# MCU.net
KiCad netlist of a schematic drawn in Altium Designer
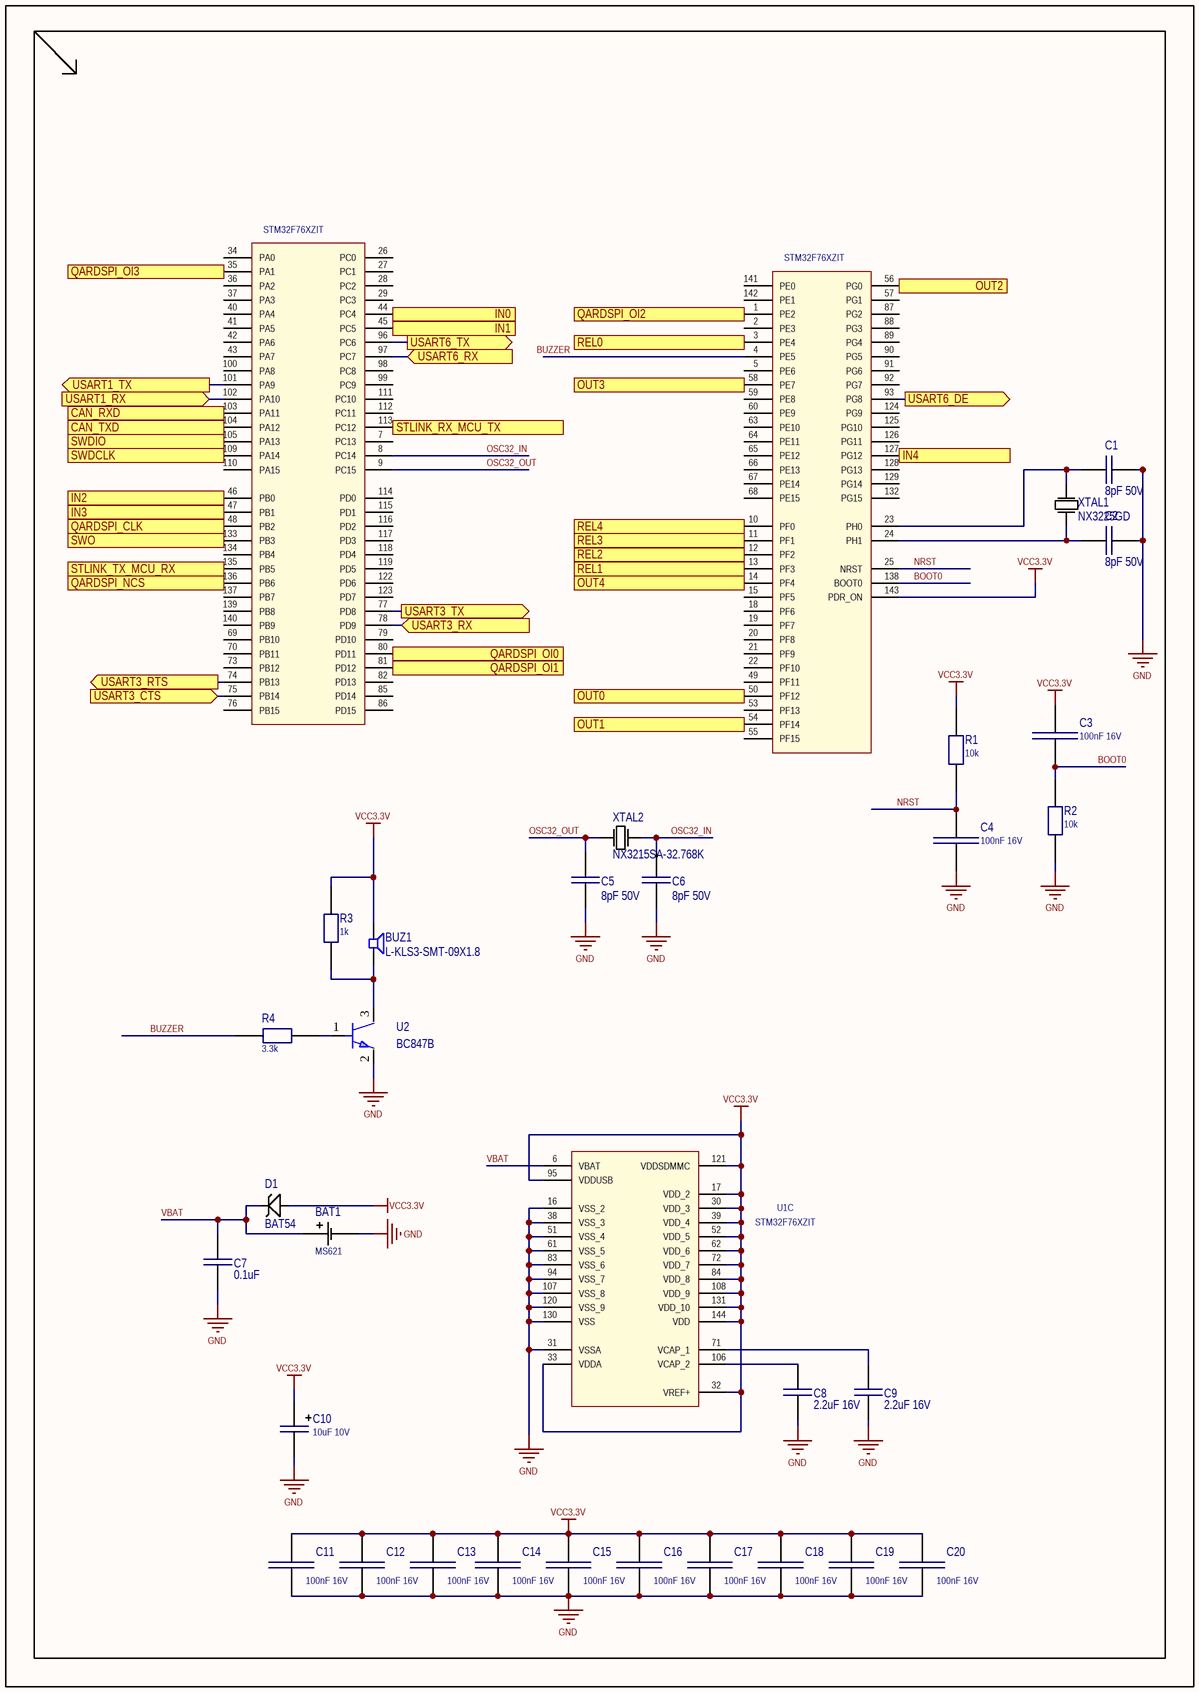
[diagram p0: MCU.SchDoc]

(export (version "E")
  (design (tool "Eeschema 10.0.6"))
  (components
    (comp (ref "BAT1")
      (value "MS621")
      (footprint "battery_socets:MS621")
      (description "Battery")
      (libsource (lib "battery_socets") (part "MS621"))
    )
    (comp (ref "BUZ1")
      (value "L-KLS3-SMT-09X1.8")
      (footprint "SPKR_PKMCS0909E4000-R1")
      (description "Piezoelectric Sounders")
      (fields (field (name "ALTERNATIVE PART") "PKLCS1212E40A1-R1"))
      (libsource (lib "other") (part "BUZZER"))
    )
    (comp (ref "C1")
      (value "8pF 50V")
      (footprint "C_0603")
      (description "Capacitor")
      (fields (field (name "PART NUMBER") "CC0603DRNPO9BN8R0"))
      (libsource (lib "capacitors") (part "CAP_SMD"))
    )
    (comp (ref "C2")
      (value "8pF 50V")
      (footprint "C_0603")
      (description "Capacitor")
      (fields (field (name "PART NUMBER") "CC0603DRNPO9BN8R0"))
      (libsource (lib "capacitors") (part "CAP_SMD"))
    )
    (comp (ref "C3")
      (value "100nF 16V")
      (footprint "C_0603")
      (description "Capacitor")
      (fields (field (name "PART NUMBER") "CC0603KPX7R9BB104"))
      (libsource (lib "AX_Altium_v2.3") (part "C0603"))
    )
    (comp (ref "C4")
      (value "100nF 16V")
      (footprint "C_0603")
      (description "Capacitor")
      (fields (field (name "PART NUMBER") "CC0603KPX7R9BB104"))
      (libsource (lib "AX_Altium_v2.3") (part "C0603"))
    )
    (comp (ref "C5")
      (value "8pF 50V")
      (footprint "C_0603")
      (description "Capacitor")
      (fields (field (name "PART NUMBER") "CC0603DRNPO9BN8R0"))
      (libsource (lib "capacitors") (part "CAP_SMD"))
    )
    (comp (ref "C6")
      (value "8pF 50V")
      (footprint "C_0603")
      (description "Capacitor")
      (fields (field (name "PART NUMBER") "CC0603DRNPO9BN8R0"))
      (libsource (lib "capacitors") (part "CAP_SMD"))
    )
    (comp (ref "C7")
      (value "0.1uF")
      (footprint "C_0603")
      (description "Capacitor")
      (fields (field (name "PART NUMBER") "CC0603KPX7R9BB104"))
      (libsource (lib "capacitors") (part "CAP_SMD"))
    )
    (comp (ref "C8")
      (value "2.2uF 16V")
      (footprint "C_0603")
      (description "Capacitor")
      (fields (field (name "PART NUMBER") "CC0603KRX5R7BB225"))
      (libsource (lib "capacitors") (part "CAP_SMD"))
    )
    (comp (ref "C9")
      (value "2.2uF 16V")
      (footprint "C_0603")
      (description "Capacitor")
      (fields (field (name "PART NUMBER") "CC0603KRX5R7BB225"))
      (libsource (lib "capacitors") (part "CAP_SMD"))
    )
    (comp (ref "C10")
      (value "10uF 10V")
      (footprint "TANTAL_TYPE_A")
      (description "Tantal Capacitor")
      (fields (field (name "PART NUMBER") "293D106X9010A2TE3"))
      (libsource (lib "capacitors") (part "TANTAL_CAP"))
    )
    (comp (ref "C11")
      (value "100nF 16V")
      (footprint "C_0603")
      (description "Capacitor")
      (fields (field (name "PART NUMBER") "CC0603KPX7R9BB104"))
      (libsource (lib "AX_Altium_v2.3") (part "C0603"))
    )
    (comp (ref "C12")
      (value "100nF 16V")
      (footprint "C_0603")
      (description "Capacitor")
      (fields (field (name "PART NUMBER") "CC0603KPX7R9BB104"))
      (libsource (lib "AX_Altium_v2.3") (part "C0603"))
    )
    (comp (ref "C13")
      (value "100nF 16V")
      (footprint "C_0603")
      (description "Capacitor")
      (fields (field (name "PART NUMBER") "CC0603KPX7R9BB104"))
      (libsource (lib "AX_Altium_v2.3") (part "C0603"))
    )
    (comp (ref "C14")
      (value "100nF 16V")
      (footprint "C_0603")
      (description "Capacitor")
      (fields (field (name "PART NUMBER") "CC0603KPX7R9BB104"))
      (libsource (lib "AX_Altium_v2.3") (part "C0603"))
    )
    (comp (ref "C15")
      (value "100nF 16V")
      (footprint "C_0603")
      (description "Capacitor")
      (fields (field (name "PART NUMBER") "CC0603KPX7R9BB104"))
      (libsource (lib "AX_Altium_v2.3") (part "C0603"))
    )
    (comp (ref "C16")
      (value "100nF 16V")
      (footprint "C_0603")
      (description "Capacitor")
      (fields (field (name "PART NUMBER") "CC0603KPX7R9BB104"))
      (libsource (lib "AX_Altium_v2.3") (part "C0603"))
    )
    (comp (ref "C17")
      (value "100nF 16V")
      (footprint "C_0603")
      (description "Capacitor")
      (fields (field (name "PART NUMBER") "CC0603KPX7R9BB104"))
      (libsource (lib "AX_Altium_v2.3") (part "C0603"))
    )
    (comp (ref "C18")
      (value "100nF 16V")
      (footprint "C_0603")
      (description "Capacitor")
      (fields (field (name "PART NUMBER") "CC0603KPX7R9BB104"))
      (libsource (lib "AX_Altium_v2.3") (part "C0603"))
    )
    (comp (ref "C19")
      (value "100nF 16V")
      (footprint "C_0603")
      (description "Capacitor")
      (fields (field (name "PART NUMBER") "CC0603KPX7R9BB104"))
      (libsource (lib "AX_Altium_v2.3") (part "C0603"))
    )
    (comp (ref "C20")
      (value "100nF 16V")
      (footprint "C_0603")
      (description "Capacitor")
      (fields (field (name "PART NUMBER") "CC0603KPX7R9BB104"))
      (libsource (lib "AX_Altium_v2.3") (part "C0603"))
    )
    (comp (ref "D1")
      (value "BAT54")
      (footprint "SOT23")
      (description "Diode")
      (libsource (lib "diode") (part "BAT54"))
    )
    (comp (ref "R1")
      (value "10k")
      (footprint "R_0603")
      (description "Resistor")
      (fields (field (name "PART NUMBER") "RC0603FR-0710KL"))
      (libsource (lib "resistors") (part "RES_SMD"))
    )
    (comp (ref "R2")
      (value "10k")
      (footprint "R_0603")
      (description "Resistor")
      (fields (field (name "PART NUMBER") "RC0603FR-0710KL"))
      (libsource (lib "resistors") (part "RES_SMD"))
    )
    (comp (ref "R3")
      (value "1k")
      (footprint "R_0603")
      (description "Resistor")
      (fields (field (name "PART NUMBER") "RC0603FR-071KL"))
      (libsource (lib "resistors") (part "RES_SMD"))
    )
    (comp (ref "R4")
      (value "3.3k")
      (footprint "R_0603")
      (description "Resistor")
      (fields (field (name "PART NUMBER") "RC0603FR-073K3L"))
      (libsource (lib "resistors") (part "RES_SMD"))
    )
    (comp (ref "U1")
      (value "STM32F76XZIT")
      (footprint "TQFP144_M")
      (fields
        (field (name "MANUFACTURER_PART_NUMBER") "STM32F76XZXT")
        (field (name "PART NUMBER") "STM32F765ZGT")
        (field (name "COPYRIGHT") "Copyright (C) 2016 Accelerated Designs. All rights reserved")
      )
      (libsource (lib "STM32 F4") (part "STM32F76XZXT"))
    )
    (comp (ref "U2") (value "BC847B") (footprint "SOT23") (libsource (lib "AX_Altium_v2.3") (part "BC847B")))
    (comp (ref "XTAL1")
      (value "NX3225GD")
      (footprint "NX3225GD")
      (description "Crystal Oscillator")
      (fields (field (name "PART NUMBER") "NX3225GD-8MHZ-EXS00A-CG05041"))
      (libsource (lib "crystals_oscillators") (part "NX3225GD"))
    )
    (comp (ref "XTAL2")
      (value "NX3215SA-32.768K")
      (footprint "XTAL_NX3215SA-32.768K-STD-MUA-8")
      (description "Crystal Oscillator")
      (fields (field (name "PART NUMBER") "NX3215SA-32.768K-10PPM-45KOHM-6PF"))
      (libsource (lib "crystals_oscillators") (part "NX3215SA-32.768K"))
    )
  )
  (nets
    (net (code "1") (name "/BOOT0") (class "Default")
      (node (ref "C3") (pin "2") (pinfunction "2_2") (pintype "passive"))
      (node (ref "R2") (pin "2") (pinfunction "2_2") (pintype "passive"))
      (node (ref "U1") (pin "138") (pinfunction "BOOT0_138") (pintype "passive"))
    )
    (net (code "2") (name "/BUZZER") (class "Default")
      (node (ref "R4") (pin "1") (pinfunction "1_1") (pintype "passive"))
      (node (ref "U1") (pin "4") (pinfunction "PE5_4") (pintype "passive"))
    )
    (net (code "3") (name "/CAN_RXD") (class "Default")
      (node (ref "U1") (pin "103") (pinfunction "PA11_103") (pintype "passive"))
    )
    (net (code "4") (name "/CAN_TXD") (class "Default")
      (node (ref "U1") (pin "104") (pinfunction "PA12_104") (pintype "passive"))
    )
    (net (code "5") (name "/IN0") (class "Default")
      (node (ref "U1") (pin "44") (pinfunction "PC4_44") (pintype "passive"))
    )
    (net (code "6") (name "/IN1") (class "Default")
      (node (ref "U1") (pin "45") (pinfunction "PC5_45") (pintype "passive"))
    )
    (net (code "7") (name "/IN2") (class "Default")
      (node (ref "U1") (pin "46") (pinfunction "PB0_46") (pintype "passive"))
    )
    (net (code "8") (name "/IN3") (class "Default")
      (node (ref "U1") (pin "47") (pinfunction "PB1_47") (pintype "passive"))
    )
    (net (code "9") (name "/IN4") (class "Default")
      (node (ref "U1") (pin "127") (pinfunction "PG12_127") (pintype "passive"))
    )
    (net (code "10") (name "/NRST") (class "Default")
      (node (ref "C4") (pin "2") (pinfunction "2_2") (pintype "passive"))
      (node (ref "R1") (pin "1") (pinfunction "1_1") (pintype "passive"))
      (node (ref "U1") (pin "25") (pinfunction "NRST_25") (pintype "passive"))
    )
    (net (code "11") (name "/OSC32_IN") (class "Default")
      (node (ref "C6") (pin "2") (pinfunction "2_2") (pintype "passive"))
      (node (ref "U1") (pin "8") (pinfunction "PC14_8") (pintype "passive"))
      (node (ref "XTAL2") (pin "2") (pinfunction "OSC2_2") (pintype "passive"))
    )
    (net (code "12") (name "/OSC32_OUT") (class "Default")
      (node (ref "C5") (pin "2") (pinfunction "2_2") (pintype "passive"))
      (node (ref "U1") (pin "9") (pinfunction "PC15_9") (pintype "passive"))
      (node (ref "XTAL2") (pin "1") (pinfunction "OSC1_1") (pintype "passive"))
    )
    (net (code "13") (name "/OUT0") (class "Default")
      (node (ref "U1") (pin "50") (pinfunction "PF12_50") (pintype "passive"))
    )
    (net (code "14") (name "/OUT1") (class "Default")
      (node (ref "U1") (pin "54") (pinfunction "PF14_54") (pintype "passive"))
    )
    (net (code "15") (name "/OUT2") (class "Default")
      (node (ref "U1") (pin "56") (pinfunction "PG0_56") (pintype "passive"))
    )
    (net (code "16") (name "/OUT3") (class "Default")
      (node (ref "U1") (pin "58") (pinfunction "PE7_58") (pintype "passive"))
    )
    (net (code "17") (name "/OUT4") (class "Default")
      (node (ref "U1") (pin "14") (pinfunction "PF4_14") (pintype "passive"))
    )
    (net (code "18") (name "/QARDSPI_CLK") (class "Default")
      (node (ref "U1") (pin "48") (pinfunction "PB2_48") (pintype "passive"))
    )
    (net (code "19") (name "/QARDSPI_NCS") (class "Default")
      (node (ref "U1") (pin "136") (pinfunction "PB6_136") (pintype "passive"))
    )
    (net (code "20") (name "/QARDSPI_OI0") (class "Default")
      (node (ref "U1") (pin "80") (pinfunction "PD11_80") (pintype "passive"))
    )
    (net (code "21") (name "/QARDSPI_OI1") (class "Default")
      (node (ref "U1") (pin "81") (pinfunction "PD12_81") (pintype "passive"))
    )
    (net (code "22") (name "/QARDSPI_OI2") (class "Default")
      (node (ref "U1") (pin "1") (pinfunction "PE2_1") (pintype "passive"))
    )
    (net (code "23") (name "/QARDSPI_OI3") (class "Default")
      (node (ref "U1") (pin "35") (pinfunction "PA1_35") (pintype "passive"))
    )
    (net (code "24") (name "/REL0") (class "Default")
      (node (ref "U1") (pin "3") (pinfunction "PE4_3") (pintype "passive"))
    )
    (net (code "25") (name "/REL1") (class "Default")
      (node (ref "U1") (pin "13") (pinfunction "PF3_13") (pintype "passive"))
    )
    (net (code "26") (name "/REL2") (class "Default")
      (node (ref "U1") (pin "12") (pinfunction "PF2_12") (pintype "passive"))
    )
    (net (code "27") (name "/REL3") (class "Default")
      (node (ref "U1") (pin "11") (pinfunction "PF1_11") (pintype "passive"))
    )
    (net (code "28") (name "/REL4") (class "Default")
      (node (ref "U1") (pin "10") (pinfunction "PF0_10") (pintype "passive"))
    )
    (net (code "29") (name "/STLINK_RX_MCU_TX") (class "Default")
      (node (ref "U1") (pin "113") (pinfunction "PC12_113") (pintype "passive"))
    )
    (net (code "30") (name "/STLINK_TX_MCU_RX") (class "Default")
      (node (ref "U1") (pin "135") (pinfunction "PB5_135") (pintype "passive"))
    )
    (net (code "31") (name "/SWDCLK") (class "Default")
      (node (ref "U1") (pin "109") (pinfunction "PA14_109") (pintype "passive"))
    )
    (net (code "32") (name "/SWDIO") (class "Default")
      (node (ref "U1") (pin "105") (pinfunction "PA13_105") (pintype "passive"))
    )
    (net (code "33") (name "/SWO") (class "Default")
      (node (ref "U1") (pin "133") (pinfunction "PB3_133") (pintype "passive"))
    )
    (net (code "34") (name "/USART1_RX") (class "Default")
      (node (ref "U1") (pin "102") (pinfunction "PA10_102") (pintype "passive"))
    )
    (net (code "35") (name "/USART1_TX") (class "Default")
      (node (ref "U1") (pin "101") (pinfunction "PA9_101") (pintype "passive"))
    )
    (net (code "36") (name "/USART3_CTS") (class "Default")
      (node (ref "U1") (pin "75") (pinfunction "PB14_75") (pintype "passive"))
    )
    (net (code "37") (name "/USART3_RTS") (class "Default")
      (node (ref "U1") (pin "74") (pinfunction "PB13_74") (pintype "passive"))
    )
    (net (code "38") (name "/USART3_RX") (class "Default")
      (node (ref "U1") (pin "78") (pinfunction "PD9_78") (pintype "passive"))
    )
    (net (code "39") (name "/USART3_TX") (class "Default")
      (node (ref "U1") (pin "77") (pinfunction "PD8_77") (pintype "passive"))
    )
    (net (code "40") (name "/USART6_DE") (class "Default")
      (node (ref "U1") (pin "93") (pinfunction "PG8_93") (pintype "passive"))
    )
    (net (code "41") (name "/USART6_RX") (class "Default")
      (node (ref "U1") (pin "97") (pinfunction "PC7_97") (pintype "passive"))
    )
    (net (code "42") (name "/USART6_TX") (class "Default")
      (node (ref "U1") (pin "96") (pinfunction "PC6_96") (pintype "passive"))
    )
    (net (code "43") (name "/VBAT") (class "Default")
      (node (ref "BAT1") (pin "1") (pinfunction "+_1") (pintype "passive"))
      (node (ref "C7") (pin "2") (pinfunction "2_2") (pintype "passive"))
      (node (ref "D1") (pin "3") (pinfunction "3_3") (pintype "passive"))
      (node (ref "U1") (pin "6") (pinfunction "VBAT_6") (pintype "passive"))
    )
    (net (code "44") (name "GND") (class "Default")
      (node (ref "BAT1") (pin "0") (pinfunction "-_0") (pintype "passive"))
      (node (ref "C1") (pin "1") (pinfunction "1_1") (pintype "passive"))
      (node (ref "C10") (pin "2") (pinfunction "2_2") (pintype "passive"))
      (node (ref "C11") (pin "1") (pinfunction "1_1") (pintype "passive"))
      (node (ref "C12") (pin "1") (pinfunction "1_1") (pintype "passive"))
      (node (ref "C13") (pin "1") (pinfunction "1_1") (pintype "passive"))
      (node (ref "C14") (pin "1") (pinfunction "1_1") (pintype "passive"))
      (node (ref "C15") (pin "1") (pinfunction "1_1") (pintype "passive"))
      (node (ref "C16") (pin "1") (pinfunction "1_1") (pintype "passive"))
      (node (ref "C17") (pin "1") (pinfunction "1_1") (pintype "passive"))
      (node (ref "C18") (pin "1") (pinfunction "1_1") (pintype "passive"))
      (node (ref "C19") (pin "1") (pinfunction "1_1") (pintype "passive"))
      (node (ref "C2") (pin "1") (pinfunction "1_1") (pintype "passive"))
      (node (ref "C20") (pin "1") (pinfunction "1_1") (pintype "passive"))
      (node (ref "C4") (pin "1") (pinfunction "1_1") (pintype "passive"))
      (node (ref "C5") (pin "1") (pinfunction "1_1") (pintype "passive"))
      (node (ref "C6") (pin "1") (pinfunction "1_1") (pintype "passive"))
      (node (ref "C7") (pin "1") (pinfunction "1_1") (pintype "passive"))
      (node (ref "C8") (pin "1") (pinfunction "1_1") (pintype "passive"))
      (node (ref "C9") (pin "1") (pinfunction "1_1") (pintype "passive"))
      (node (ref "R2") (pin "1") (pinfunction "1_1") (pintype "passive"))
      (node (ref "U1") (pin "107") (pinfunction "VSS_8_107") (pintype "passive"))
      (node (ref "U1") (pin "120") (pinfunction "VSS_9_120") (pintype "passive"))
      (node (ref "U1") (pin "130") (pinfunction "VSS_130") (pintype "passive"))
      (node (ref "U1") (pin "16") (pinfunction "VSS_2_16") (pintype "passive"))
      (node (ref "U1") (pin "31") (pinfunction "VSSA_31") (pintype "passive"))
      (node (ref "U1") (pin "38") (pinfunction "VSS_3_38") (pintype "passive"))
      (node (ref "U1") (pin "51") (pinfunction "VSS_4_51") (pintype "passive"))
      (node (ref "U1") (pin "61") (pinfunction "VSS_5_61") (pintype "passive"))
      (node (ref "U1") (pin "83") (pinfunction "VSS_6_83") (pintype "passive"))
      (node (ref "U1") (pin "94") (pinfunction "VSS_7_94") (pintype "passive"))
      (node (ref "U2") (pin "2") (pintype "passive"))
    )
    (net (code "45") (name "Net-(BUZ1-Pad2)") (class "Default")
      (node (ref "BUZ1") (pin "2") (pinfunction "2_2") (pintype "passive"))
      (node (ref "R3") (pin "1") (pinfunction "1_1") (pintype "passive"))
      (node (ref "U2") (pin "3") (pintype "passive"))
    )
    (net (code "46") (name "Net-(R4-Pad2)") (class "Default")
      (node (ref "R4") (pin "2") (pinfunction "2_2") (pintype "passive"))
      (node (ref "U2") (pin "1") (pintype "passive"))
    )
    (net (code "47") (name "Net-(U1B-PH0)") (class "Default")
      (node (ref "C1") (pin "2") (pinfunction "2_2") (pintype "passive"))
      (node (ref "U1") (pin "23") (pinfunction "PH0_23") (pintype "passive"))
      (node (ref "XTAL1") (pin "2") (pinfunction "OSC2_2") (pintype "passive"))
    )
    (net (code "48") (name "Net-(U1B-PH1)") (class "Default")
      (node (ref "C2") (pin "2") (pinfunction "2_2") (pintype "passive"))
      (node (ref "U1") (pin "24") (pinfunction "PH1_24") (pintype "passive"))
      (node (ref "XTAL1") (pin "1") (pinfunction "OSC1_1") (pintype "passive"))
    )
    (net (code "49") (name "Net-(U1C-VCAP_1)") (class "Default")
      (node (ref "C9") (pin "2") (pinfunction "2_2") (pintype "passive"))
      (node (ref "U1") (pin "71") (pinfunction "VCAP_1_71") (pintype "passive"))
    )
    (net (code "50") (name "Net-(U1C-VCAP_2)") (class "Default")
      (node (ref "C8") (pin "2") (pinfunction "2_2") (pintype "passive"))
      (node (ref "U1") (pin "106") (pinfunction "VCAP_2_106") (pintype "passive"))
    )
    (net (code "51") (name "VCC3.3V") (class "Default")
      (node (ref "BUZ1") (pin "1") (pinfunction "1_1") (pintype "passive"))
      (node (ref "C10") (pin "1") (pinfunction "1_1") (pintype "passive"))
      (node (ref "C11") (pin "2") (pinfunction "2_2") (pintype "passive"))
      (node (ref "C12") (pin "2") (pinfunction "2_2") (pintype "passive"))
      (node (ref "C13") (pin "2") (pinfunction "2_2") (pintype "passive"))
      (node (ref "C14") (pin "2") (pinfunction "2_2") (pintype "passive"))
      (node (ref "C15") (pin "2") (pinfunction "2_2") (pintype "passive"))
      (node (ref "C16") (pin "2") (pinfunction "2_2") (pintype "passive"))
      (node (ref "C17") (pin "2") (pinfunction "2_2") (pintype "passive"))
      (node (ref "C18") (pin "2") (pinfunction "2_2") (pintype "passive"))
      (node (ref "C19") (pin "2") (pinfunction "2_2") (pintype "passive"))
      (node (ref "C20") (pin "2") (pinfunction "2_2") (pintype "passive"))
      (node (ref "C3") (pin "1") (pinfunction "1_1") (pintype "passive"))
      (node (ref "D1") (pin "1") (pinfunction "1_1") (pintype "passive"))
      (node (ref "R1") (pin "2") (pinfunction "2_2") (pintype "passive"))
      (node (ref "R3") (pin "2") (pinfunction "2_2") (pintype "passive"))
      (node (ref "U1") (pin "108") (pinfunction "VDD_9_108") (pintype "passive"))
      (node (ref "U1") (pin "121") (pinfunction "VDDSDMMC_121") (pintype "passive"))
      (node (ref "U1") (pin "131") (pinfunction "VDD_10_131") (pintype "passive"))
      (node (ref "U1") (pin "143") (pinfunction "PDR_ON_143") (pintype "passive"))
      (node (ref "U1") (pin "144") (pinfunction "VDD_144") (pintype "passive"))
      (node (ref "U1") (pin "17") (pinfunction "VDD_2_17") (pintype "passive"))
      (node (ref "U1") (pin "30") (pinfunction "VDD_3_30") (pintype "passive"))
      (node (ref "U1") (pin "32") (pinfunction "VREF+_32") (pintype "passive"))
      (node (ref "U1") (pin "33") (pinfunction "VDDA_33") (pintype "passive"))
      (node (ref "U1") (pin "39") (pinfunction "VDD_4_39") (pintype "passive"))
      (node (ref "U1") (pin "52") (pinfunction "VDD_5_52") (pintype "passive"))
      (node (ref "U1") (pin "62") (pinfunction "VDD_6_62") (pintype "passive"))
      (node (ref "U1") (pin "72") (pinfunction "VDD_7_72") (pintype "passive"))
      (node (ref "U1") (pin "84") (pinfunction "VDD_8_84") (pintype "passive"))
      (node (ref "U1") (pin "95") (pinfunction "VDDUSB_95") (pintype "passive"))
    )
    (net (code "52") (name "unconnected-(U1A-PA0-Pad34)") (class "Default")
      (node (ref "U1") (pin "34") (pinfunction "PA0_34") (pintype "passive"))
    )
    (net (code "53") (name "unconnected-(U1A-PA2-Pad36)") (class "Default")
      (node (ref "U1") (pin "36") (pinfunction "PA2_36") (pintype "passive"))
    )
    (net (code "54") (name "unconnected-(U1A-PA3-Pad37)") (class "Default")
      (node (ref "U1") (pin "37") (pinfunction "PA3_37") (pintype "passive"))
    )
    (net (code "55") (name "unconnected-(U1A-PA4-Pad40)") (class "Default")
      (node (ref "U1") (pin "40") (pinfunction "PA4_40") (pintype "passive"))
    )
    (net (code "56") (name "unconnected-(U1A-PA5-Pad41)") (class "Default")
      (node (ref "U1") (pin "41") (pinfunction "PA5_41") (pintype "passive"))
    )
    (net (code "57") (name "unconnected-(U1A-PA6-Pad42)") (class "Default")
      (node (ref "U1") (pin "42") (pinfunction "PA6_42") (pintype "passive"))
    )
    (net (code "58") (name "unconnected-(U1A-PA7-Pad43)") (class "Default")
      (node (ref "U1") (pin "43") (pinfunction "PA7_43") (pintype "passive"))
    )
    (net (code "59") (name "unconnected-(U1A-PA8-Pad100)") (class "Default")
      (node (ref "U1") (pin "100") (pinfunction "PA8_100") (pintype "passive"))
    )
    (net (code "60") (name "unconnected-(U1A-PA15-Pad110)") (class "Default")
      (node (ref "U1") (pin "110") (pinfunction "PA15_110") (pintype "passive"))
    )
    (net (code "61") (name "unconnected-(U1A-PB4-Pad134)") (class "Default")
      (node (ref "U1") (pin "134") (pinfunction "PB4_134") (pintype "passive"))
    )
    (net (code "62") (name "unconnected-(U1A-PB7-Pad137)") (class "Default")
      (node (ref "U1") (pin "137") (pinfunction "PB7_137") (pintype "passive"))
    )
    (net (code "63") (name "unconnected-(U1A-PB8-Pad139)") (class "Default")
      (node (ref "U1") (pin "139") (pinfunction "PB8_139") (pintype "passive"))
    )
    (net (code "64") (name "unconnected-(U1A-PB9-Pad140)") (class "Default")
      (node (ref "U1") (pin "140") (pinfunction "PB9_140") (pintype "passive"))
    )
    (net (code "65") (name "unconnected-(U1A-PB10-Pad69)") (class "Default")
      (node (ref "U1") (pin "69") (pinfunction "PB10_69") (pintype "passive"))
    )
    (net (code "66") (name "unconnected-(U1A-PB11-Pad70)") (class "Default")
      (node (ref "U1") (pin "70") (pinfunction "PB11_70") (pintype "passive"))
    )
    (net (code "67") (name "unconnected-(U1A-PB12-Pad73)") (class "Default")
      (node (ref "U1") (pin "73") (pinfunction "PB12_73") (pintype "passive"))
    )
    (net (code "68") (name "unconnected-(U1A-PB15-Pad76)") (class "Default")
      (node (ref "U1") (pin "76") (pinfunction "PB15_76") (pintype "passive"))
    )
    (net (code "69") (name "unconnected-(U1A-PC0-Pad26)") (class "Default")
      (node (ref "U1") (pin "26") (pinfunction "PC0_26") (pintype "passive"))
    )
    (net (code "70") (name "unconnected-(U1A-PC1-Pad27)") (class "Default")
      (node (ref "U1") (pin "27") (pinfunction "PC1_27") (pintype "passive"))
    )
    (net (code "71") (name "unconnected-(U1A-PC2-Pad28)") (class "Default")
      (node (ref "U1") (pin "28") (pinfunction "PC2_28") (pintype "passive"))
    )
    (net (code "72") (name "unconnected-(U1A-PC3-Pad29)") (class "Default")
      (node (ref "U1") (pin "29") (pinfunction "PC3_29") (pintype "passive"))
    )
    (net (code "73") (name "unconnected-(U1A-PC8-Pad98)") (class "Default")
      (node (ref "U1") (pin "98") (pinfunction "PC8_98") (pintype "passive"))
    )
    (net (code "74") (name "unconnected-(U1A-PC9-Pad99)") (class "Default")
      (node (ref "U1") (pin "99") (pinfunction "PC9_99") (pintype "passive"))
    )
    (net (code "75") (name "unconnected-(U1A-PC10-Pad111)") (class "Default")
      (node (ref "U1") (pin "111") (pinfunction "PC10_111") (pintype "passive"))
    )
    (net (code "76") (name "unconnected-(U1A-PC11-Pad112)") (class "Default")
      (node (ref "U1") (pin "112") (pinfunction "PC11_112") (pintype "passive"))
    )
    (net (code "77") (name "unconnected-(U1A-PC13-Pad7)") (class "Default")
      (node (ref "U1") (pin "7") (pinfunction "PC13_7") (pintype "passive"))
    )
    (net (code "78") (name "unconnected-(U1A-PD0-Pad114)") (class "Default")
      (node (ref "U1") (pin "114") (pinfunction "PD0_114") (pintype "passive"))
    )
    (net (code "79") (name "unconnected-(U1A-PD1-Pad115)") (class "Default")
      (node (ref "U1") (pin "115") (pinfunction "PD1_115") (pintype "passive"))
    )
    (net (code "80") (name "unconnected-(U1A-PD2-Pad116)") (class "Default")
      (node (ref "U1") (pin "116") (pinfunction "PD2_116") (pintype "passive"))
    )
    (net (code "81") (name "unconnected-(U1A-PD3-Pad117)") (class "Default")
      (node (ref "U1") (pin "117") (pinfunction "PD3_117") (pintype "passive"))
    )
    (net (code "82") (name "unconnected-(U1A-PD4-Pad118)") (class "Default")
      (node (ref "U1") (pin "118") (pinfunction "PD4_118") (pintype "passive"))
    )
    (net (code "83") (name "unconnected-(U1A-PD5-Pad119)") (class "Default")
      (node (ref "U1") (pin "119") (pinfunction "PD5_119") (pintype "passive"))
    )
    (net (code "84") (name "unconnected-(U1A-PD6-Pad122)") (class "Default")
      (node (ref "U1") (pin "122") (pinfunction "PD6_122") (pintype "passive"))
    )
    (net (code "85") (name "unconnected-(U1A-PD7-Pad123)") (class "Default")
      (node (ref "U1") (pin "123") (pinfunction "PD7_123") (pintype "passive"))
    )
    (net (code "86") (name "unconnected-(U1A-PD10-Pad79)") (class "Default")
      (node (ref "U1") (pin "79") (pinfunction "PD10_79") (pintype "passive"))
    )
    (net (code "87") (name "unconnected-(U1A-PD13-Pad82)") (class "Default")
      (node (ref "U1") (pin "82") (pinfunction "PD13_82") (pintype "passive"))
    )
    (net (code "88") (name "unconnected-(U1A-PD14-Pad85)") (class "Default")
      (node (ref "U1") (pin "85") (pinfunction "PD14_85") (pintype "passive"))
    )
    (net (code "89") (name "unconnected-(U1A-PD15-Pad86)") (class "Default")
      (node (ref "U1") (pin "86") (pinfunction "PD15_86") (pintype "passive"))
    )
    (net (code "90") (name "unconnected-(U1B-PE0-Pad141)") (class "Default")
      (node (ref "U1") (pin "141") (pinfunction "PE0_141") (pintype "passive"))
    )
    (net (code "91") (name "unconnected-(U1B-PE1-Pad142)") (class "Default")
      (node (ref "U1") (pin "142") (pinfunction "PE1_142") (pintype "passive"))
    )
    (net (code "92") (name "unconnected-(U1B-PE3-Pad2)") (class "Default")
      (node (ref "U1") (pin "2") (pinfunction "PE3_2") (pintype "passive"))
    )
    (net (code "93") (name "unconnected-(U1B-PE6-Pad5)") (class "Default")
      (node (ref "U1") (pin "5") (pinfunction "PE6_5") (pintype "passive"))
    )
    (net (code "94") (name "unconnected-(U1B-PE8-Pad59)") (class "Default")
      (node (ref "U1") (pin "59") (pinfunction "PE8_59") (pintype "passive"))
    )
    (net (code "95") (name "unconnected-(U1B-PE9-Pad60)") (class "Default")
      (node (ref "U1") (pin "60") (pinfunction "PE9_60") (pintype "passive"))
    )
    (net (code "96") (name "unconnected-(U1B-PE10-Pad63)") (class "Default")
      (node (ref "U1") (pin "63") (pinfunction "PE10_63") (pintype "passive"))
    )
    (net (code "97") (name "unconnected-(U1B-PE11-Pad64)") (class "Default")
      (node (ref "U1") (pin "64") (pinfunction "PE11_64") (pintype "passive"))
    )
    (net (code "98") (name "unconnected-(U1B-PE12-Pad65)") (class "Default")
      (node (ref "U1") (pin "65") (pinfunction "PE12_65") (pintype "passive"))
    )
    (net (code "99") (name "unconnected-(U1B-PE13-Pad66)") (class "Default")
      (node (ref "U1") (pin "66") (pinfunction "PE13_66") (pintype "passive"))
    )
    (net (code "100") (name "unconnected-(U1B-PE14-Pad67)") (class "Default")
      (node (ref "U1") (pin "67") (pinfunction "PE14_67") (pintype "passive"))
    )
    (net (code "101") (name "unconnected-(U1B-PE15-Pad68)") (class "Default")
      (node (ref "U1") (pin "68") (pinfunction "PE15_68") (pintype "passive"))
    )
    (net (code "102") (name "unconnected-(U1B-PF5-Pad15)") (class "Default")
      (node (ref "U1") (pin "15") (pinfunction "PF5_15") (pintype "passive"))
    )
    (net (code "103") (name "unconnected-(U1B-PF6-Pad18)") (class "Default")
      (node (ref "U1") (pin "18") (pinfunction "PF6_18") (pintype "passive"))
    )
    (net (code "104") (name "unconnected-(U1B-PF7-Pad19)") (class "Default")
      (node (ref "U1") (pin "19") (pinfunction "PF7_19") (pintype "passive"))
    )
    (net (code "105") (name "unconnected-(U1B-PF8-Pad20)") (class "Default")
      (node (ref "U1") (pin "20") (pinfunction "PF8_20") (pintype "passive"))
    )
    (net (code "106") (name "unconnected-(U1B-PF9-Pad21)") (class "Default")
      (node (ref "U1") (pin "21") (pinfunction "PF9_21") (pintype "passive"))
    )
    (net (code "107") (name "unconnected-(U1B-PF10-Pad22)") (class "Default")
      (node (ref "U1") (pin "22") (pinfunction "PF10_22") (pintype "passive"))
    )
    (net (code "108") (name "unconnected-(U1B-PF11-Pad49)") (class "Default")
      (node (ref "U1") (pin "49") (pinfunction "PF11_49") (pintype "passive"))
    )
    (net (code "109") (name "unconnected-(U1B-PF13-Pad53)") (class "Default")
      (node (ref "U1") (pin "53") (pinfunction "PF13_53") (pintype "passive"))
    )
    (net (code "110") (name "unconnected-(U1B-PF15-Pad55)") (class "Default")
      (node (ref "U1") (pin "55") (pinfunction "PF15_55") (pintype "passive"))
    )
    (net (code "111") (name "unconnected-(U1B-PG1-Pad57)") (class "Default")
      (node (ref "U1") (pin "57") (pinfunction "PG1_57") (pintype "passive"))
    )
    (net (code "112") (name "unconnected-(U1B-PG2-Pad87)") (class "Default")
      (node (ref "U1") (pin "87") (pinfunction "PG2_87") (pintype "passive"))
    )
    (net (code "113") (name "unconnected-(U1B-PG3-Pad88)") (class "Default")
      (node (ref "U1") (pin "88") (pinfunction "PG3_88") (pintype "passive"))
    )
    (net (code "114") (name "unconnected-(U1B-PG4-Pad89)") (class "Default")
      (node (ref "U1") (pin "89") (pinfunction "PG4_89") (pintype "passive"))
    )
    (net (code "115") (name "unconnected-(U1B-PG5-Pad90)") (class "Default")
      (node (ref "U1") (pin "90") (pinfunction "PG5_90") (pintype "passive"))
    )
    (net (code "116") (name "unconnected-(U1B-PG6-Pad91)") (class "Default")
      (node (ref "U1") (pin "91") (pinfunction "PG6_91") (pintype "passive"))
    )
    (net (code "117") (name "unconnected-(U1B-PG7-Pad92)") (class "Default")
      (node (ref "U1") (pin "92") (pinfunction "PG7_92") (pintype "passive"))
    )
    (net (code "118") (name "unconnected-(U1B-PG9-Pad124)") (class "Default")
      (node (ref "U1") (pin "124") (pinfunction "PG9_124") (pintype "passive"))
    )
    (net (code "119") (name "unconnected-(U1B-PG10-Pad125)") (class "Default")
      (node (ref "U1") (pin "125") (pinfunction "PG10_125") (pintype "passive"))
    )
    (net (code "120") (name "unconnected-(U1B-PG11-Pad126)") (class "Default")
      (node (ref "U1") (pin "126") (pinfunction "PG11_126") (pintype "passive"))
    )
    (net (code "121") (name "unconnected-(U1B-PG13-Pad128)") (class "Default")
      (node (ref "U1") (pin "128") (pinfunction "PG13_128") (pintype "passive"))
    )
    (net (code "122") (name "unconnected-(U1B-PG14-Pad129)") (class "Default")
      (node (ref "U1") (pin "129") (pinfunction "PG14_129") (pintype "passive"))
    )
    (net (code "123") (name "unconnected-(U1B-PG15-Pad132)") (class "Default")
      (node (ref "U1") (pin "132") (pinfunction "PG15_132") (pintype "passive"))
    )
  )
)
